# TAG.net
KiCad netlist of a schematic drawn in Altium Designer
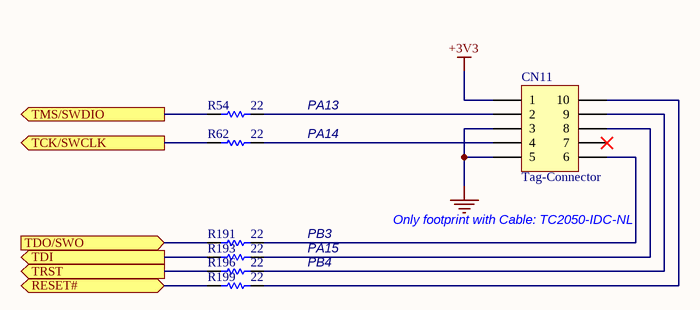
[diagram p0: TAG.SchDoc]

(export (version "E")
  (design (tool "Eeschema 10.0.6"))
  (components
    (comp (ref "CN11")
      (value "Tag-Connector")
      (footprint "TC2050-IDC-NL")
      (description "Header, 6-Pin, Dual row")
      (fields (field (name "PUBLISHER") "Altium Limited"))
      (libsource (lib "MB1248_1") (part "Tag-Connector"))
    )
    (comp (ref "R54")
      (value "22")
      (footprint "0603R")
      (description "Resistor")
      (fields (field (name "PUBLISHER") "Altium Limited"))
      (libsource (lib "Miscellaneous Devices") (part "Res1"))
    )
    (comp (ref "R62")
      (value "22")
      (footprint "0603R")
      (description "Resistor")
      (fields (field (name "PUBLISHER") "Altium Limited"))
      (libsource (lib "Miscellaneous Devices") (part "Res1"))
    )
    (comp (ref "R191")
      (value "22")
      (footprint "0603R")
      (description "Resistor")
      (fields (field (name "PUBLISHER") "Altium Limited"))
      (libsource (lib "Miscellaneous Devices") (part "Res1"))
    )
    (comp (ref "R193")
      (value "22")
      (footprint "0603R")
      (description "Resistor")
      (fields (field (name "PUBLISHER") "Altium Limited"))
      (libsource (lib "Miscellaneous Devices") (part "Res1"))
    )
    (comp (ref "R196")
      (value "22")
      (footprint "0603R")
      (description "Resistor")
      (fields (field (name "PUBLISHER") "Altium Limited"))
      (libsource (lib "Miscellaneous Devices") (part "Res1"))
    )
    (comp (ref "R199")
      (value "22")
      (footprint "0603R")
      (description "Resistor")
      (fields (field (name "PUBLISHER") "Altium Limited"))
      (libsource (lib "Miscellaneous Devices") (part "Res1"))
    )
  )
  (nets
    (net (code "1") (name "+3V3") (class "Default")
      (node (ref "CN11") (pin "1") (pinfunction "1_1") (pintype "passive"))
    )
    (net (code "2") (name "/RESET#") (class "Default")
      (node (ref "R199") (pin "2") (pinfunction "2_2") (pintype "passive"))
    )
    (net (code "3") (name "/TCK{slash}SWCLK") (class "Default")
      (node (ref "R62") (pin "2") (pinfunction "2_2") (pintype "passive"))
    )
    (net (code "4") (name "/TDI") (class "Default")
      (node (ref "R193") (pin "2") (pinfunction "2_2") (pintype "passive"))
    )
    (net (code "5") (name "/TDO{slash}SWO") (class "Default")
      (node (ref "R191") (pin "2") (pinfunction "2_2") (pintype "passive"))
    )
    (net (code "6") (name "/TMS{slash}SWDIO") (class "Default")
      (node (ref "R54") (pin "2") (pinfunction "2_2") (pintype "passive"))
    )
    (net (code "7") (name "/TRST") (class "Default")
      (node (ref "R196") (pin "2") (pinfunction "2_2") (pintype "passive"))
    )
    (net (code "8") (name "GND") (class "Default")
      (node (ref "CN11") (pin "3") (pinfunction "3_3") (pintype "passive"))
      (node (ref "CN11") (pin "5") (pinfunction "5_5") (pintype "passive"))
    )
    (net (code "9") (name "Net-(CN11-Pad2)") (class "Default")
      (node (ref "CN11") (pin "2") (pinfunction "2_2") (pintype "passive"))
      (node (ref "R54") (pin "1") (pinfunction "1_1") (pintype "passive"))
    )
    (net (code "10") (name "Net-(CN11-Pad4)") (class "Default")
      (node (ref "CN11") (pin "4") (pinfunction "4_4") (pintype "passive"))
      (node (ref "R62") (pin "1") (pinfunction "1_1") (pintype "passive"))
    )
    (net (code "11") (name "Net-(CN11-Pad6)") (class "Default")
      (node (ref "CN11") (pin "6") (pinfunction "6_6") (pintype "passive"))
      (node (ref "R191") (pin "1") (pinfunction "1_1") (pintype "passive"))
    )
    (net (code "12") (name "Net-(CN11-Pad8)") (class "Default")
      (node (ref "CN11") (pin "8") (pinfunction "8_8") (pintype "passive"))
      (node (ref "R193") (pin "1") (pinfunction "1_1") (pintype "passive"))
    )
    (net (code "13") (name "Net-(CN11-Pad9)") (class "Default")
      (node (ref "CN11") (pin "9") (pinfunction "9_9") (pintype "passive"))
      (node (ref "R196") (pin "1") (pinfunction "1_1") (pintype "passive"))
    )
    (net (code "14") (name "Net-(CN11-Pad10)") (class "Default")
      (node (ref "CN11") (pin "10") (pinfunction "10_10") (pintype "passive"))
      (node (ref "R199") (pin "1") (pinfunction "1_1") (pintype "passive"))
    )
    (net (code "15") (name "unconnected-(CN11-Pad7)") (class "Default")
      (node (ref "CN11") (pin "7") (pinfunction "7_7") (pintype "passive+no_connect"))
    )
  )
)
